# Regulator.net
KiCad netlist of a schematic drawn in Altium Designer
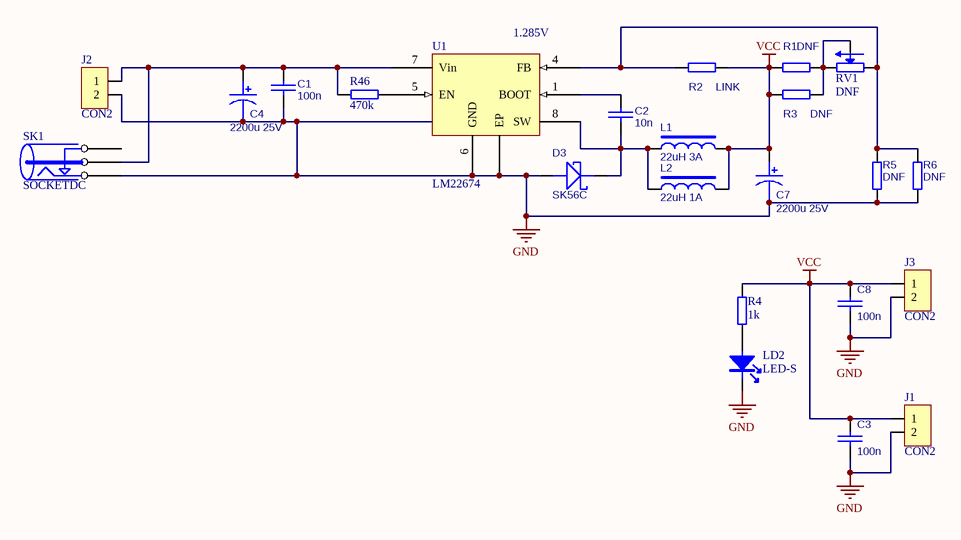
[diagram p0: Regulator.SchDoc]

(export (version "E")
  (design (tool "Eeschema 10.0.6"))
  (components
    (comp (ref "C1") (value "100n") (footprint "0603") (libsource (lib "*") (part "CAP")))
    (comp (ref "C2") (value "10n") (footprint "0603") (libsource (lib "*") (part "CAP")))
    (comp (ref "C3") (value "100n") (footprint "0603") (libsource (lib "*") (part "CAP")))
    (comp (ref "C4")
      (value "2200u 25V")
      (footprint "RB.2/.5")
      (libsource (lib "DEVICE") (part "CAPACITOR POL"))
    )
    (comp (ref "C7")
      (value "2200u 25V")
      (footprint "RB.2/.5")
      (libsource (lib "DEVICE") (part "CAPACITOR POL"))
    )
    (comp (ref "C8") (value "100n") (footprint "0603") (libsource (lib "*") (part "CAP")))
    (comp (ref "D3") (value "SK56C") (footprint "SMC") (libsource (lib "DEVICE") (part "DIODE SCHOTTKY")))
    (comp (ref "J1") (value "CON2") (footprint "Terms5mm2") (libsource (lib "DEVICE") (part "CON2")))
    (comp (ref "J2") (value "CON2") (footprint "Terms5mm2") (libsource (lib "") (part "CON2_1")))
    (comp (ref "J3") (value "CON2") (footprint "Terms5mm2") (libsource (lib "DEVICE") (part "CON2")))
    (comp (ref "L1") (value "22uH 3A") (footprint "INDUCTOR3A") (libsource (lib "*") (part "INDUCTOR2")))
    (comp (ref "L2") (value "22uH 1A") (footprint "INDUCTOR6B") (libsource (lib "*") (part "INDUCTOR2")))
    (comp (ref "LD2")
      (value "LED-S")
      (footprint "0805Diode")
      (description "LED")
      (libsource (lib "DEVICE") (part "LED-S"))
    )
    (comp (ref "R1") (value "DNF") (footprint "0603") (libsource (lib "*") (part "RES8")))
    (comp (ref "R2") (value "LINK") (footprint "0603") (libsource (lib "*") (part "RES8")))
    (comp (ref "R3") (value "DNF") (footprint "0603") (libsource (lib "*") (part "RES8")))
    (comp (ref "R4") (value "1k") (footprint "0603") (libsource (lib "DEVICE") (part "RES8")))
    (comp (ref "R5") (value "DNF") (footprint "0603") (libsource (lib "*") (part "RES8")))
    (comp (ref "R6") (value "DNF") (footprint "0603") (libsource (lib "*") (part "RES8")))
    (comp (ref "R46") (value "470k") (footprint "0603") (libsource (lib "DEVICE") (part "RES8")))
    (comp (ref "RV1") (value "DNF") (footprint "VR3362P") (libsource (lib "DEVICE") (part "RES6")))
    (comp (ref "SK1")
      (value "SOCKETDC")
      (footprint "SKTPWR")
      (description "DC Power Connector")
      (libsource (lib "*") (part "SOCKETDC"))
    )
    (comp (ref "U1")
      (value "LM22674")
      (footprint "PSOP-8")
      (description "1A SMPS")
      (libsource (lib "NS-EXTRA") (part "LM22675"))
    )
  )
  (nets
    (net (code "1") (name "GND") (class "Default")
      (node (ref "C1") (pin "1") (pintype "passive"))
      (node (ref "C3") (pin "2") (pintype "passive"))
      (node (ref "C4") (pin "2") (pinfunction "2_2") (pintype "passive"))
      (node (ref "C7") (pin "2") (pinfunction "2_2") (pintype "passive"))
      (node (ref "C8") (pin "2") (pintype "passive"))
      (node (ref "D3") (pin "A") (pinfunction "A_A") (pintype "passive"))
      (node (ref "J1") (pin "2") (pinfunction "2_2") (pintype "passive"))
      (node (ref "J2") (pin "2") (pinfunction "2_2") (pintype "passive"))
      (node (ref "J3") (pin "2") (pinfunction "2_2") (pintype "passive"))
      (node (ref "LD2") (pin "K") (pintype "passive"))
      (node (ref "R5") (pin "1") (pintype "passive"))
      (node (ref "R6") (pin "1") (pintype "passive"))
      (node (ref "SK1") (pin "COM") (pinfunction "COM_COM") (pintype "passive"))
      (node (ref "U1") (pin "6") (pinfunction "GND_6") (pintype "power_in"))
      (node (ref "U1") (pin "9") (pinfunction "EP_9") (pintype "power_in"))
    )
    (net (code "2") (name "Net-(LD2-PadA)") (class "Default")
      (node (ref "LD2") (pin "A") (pintype "passive"))
      (node (ref "R4") (pin "2") (pintype "passive"))
    )
    (net (code "3") (name "Net-(R1-Pad1)") (class "Default")
      (node (ref "R1") (pin "1") (pintype "passive"))
      (node (ref "R3") (pin "1") (pintype "passive"))
      (node (ref "RV1") (pin "CW") (pinfunction "CW_CW") (pintype "passive"))
      (node (ref "RV1") (pin "W") (pinfunction "W_W") (pintype "passive"))
    )
    (net (code "4") (name "Net-(U1-BOOT)") (class "Default")
      (node (ref "C2") (pin "1") (pintype "passive"))
      (node (ref "U1") (pin "1") (pinfunction "BOOT_1") (pintype "input"))
    )
    (net (code "5") (name "Net-(U1-EN)") (class "Default")
      (node (ref "R46") (pin "1") (pintype "passive"))
      (node (ref "U1") (pin "5") (pinfunction "EN_5") (pintype "input"))
    )
    (net (code "6") (name "Net-(U1-FB)") (class "Default")
      (node (ref "R2") (pin "2") (pintype "passive"))
      (node (ref "R5") (pin "2") (pintype "passive"))
      (node (ref "R6") (pin "2") (pintype "passive"))
      (node (ref "RV1") (pin "CCW") (pinfunction "CCW_CCW") (pintype "passive"))
      (node (ref "U1") (pin "4") (pinfunction "FB_4") (pintype "input"))
    )
    (net (code "7") (name "Net-(U1-SW)") (class "Default")
      (node (ref "C2") (pin "2") (pintype "passive"))
      (node (ref "D3") (pin "K") (pinfunction "K_K") (pintype "passive"))
      (node (ref "L1") (pin "1") (pintype "passive"))
      (node (ref "L2") (pin "1") (pintype "passive"))
      (node (ref "U1") (pin "8") (pinfunction "SW_8") (pintype "power_in"))
    )
    (net (code "8") (name "Net-(U1-Vin)") (class "Default")
      (node (ref "C1") (pin "2") (pintype "passive"))
      (node (ref "C4") (pin "1") (pinfunction "1_1") (pintype "passive"))
      (node (ref "J2") (pin "1") (pinfunction "1_1") (pintype "passive"))
      (node (ref "R46") (pin "2") (pintype "passive"))
      (node (ref "SK1") (pin "PIN") (pinfunction "PIN_PIN") (pintype "passive"))
      (node (ref "U1") (pin "7") (pinfunction "Vin_7") (pintype "passive"))
    )
    (net (code "9") (name "VCC") (class "Default")
      (node (ref "C3") (pin "1") (pintype "passive"))
      (node (ref "C7") (pin "1") (pinfunction "1_1") (pintype "passive"))
      (node (ref "C8") (pin "1") (pintype "passive"))
      (node (ref "J1") (pin "1") (pinfunction "1_1") (pintype "passive"))
      (node (ref "J3") (pin "1") (pinfunction "1_1") (pintype "passive"))
      (node (ref "L1") (pin "2") (pintype "passive"))
      (node (ref "L2") (pin "2") (pintype "passive"))
      (node (ref "R1") (pin "2") (pintype "passive"))
      (node (ref "R2") (pin "1") (pintype "passive"))
      (node (ref "R3") (pin "2") (pintype "passive"))
      (node (ref "R4") (pin "1") (pintype "passive"))
    )
    (net (code "10") (name "unconnected-(SK1-PadSW)") (class "Default")
      (node (ref "SK1") (pin "SW") (pinfunction "SW_SW") (pintype "passive"))
    )
  )
)
